# 1G_Eternet.net
KiCad netlist of a schematic drawn in Altium Designer
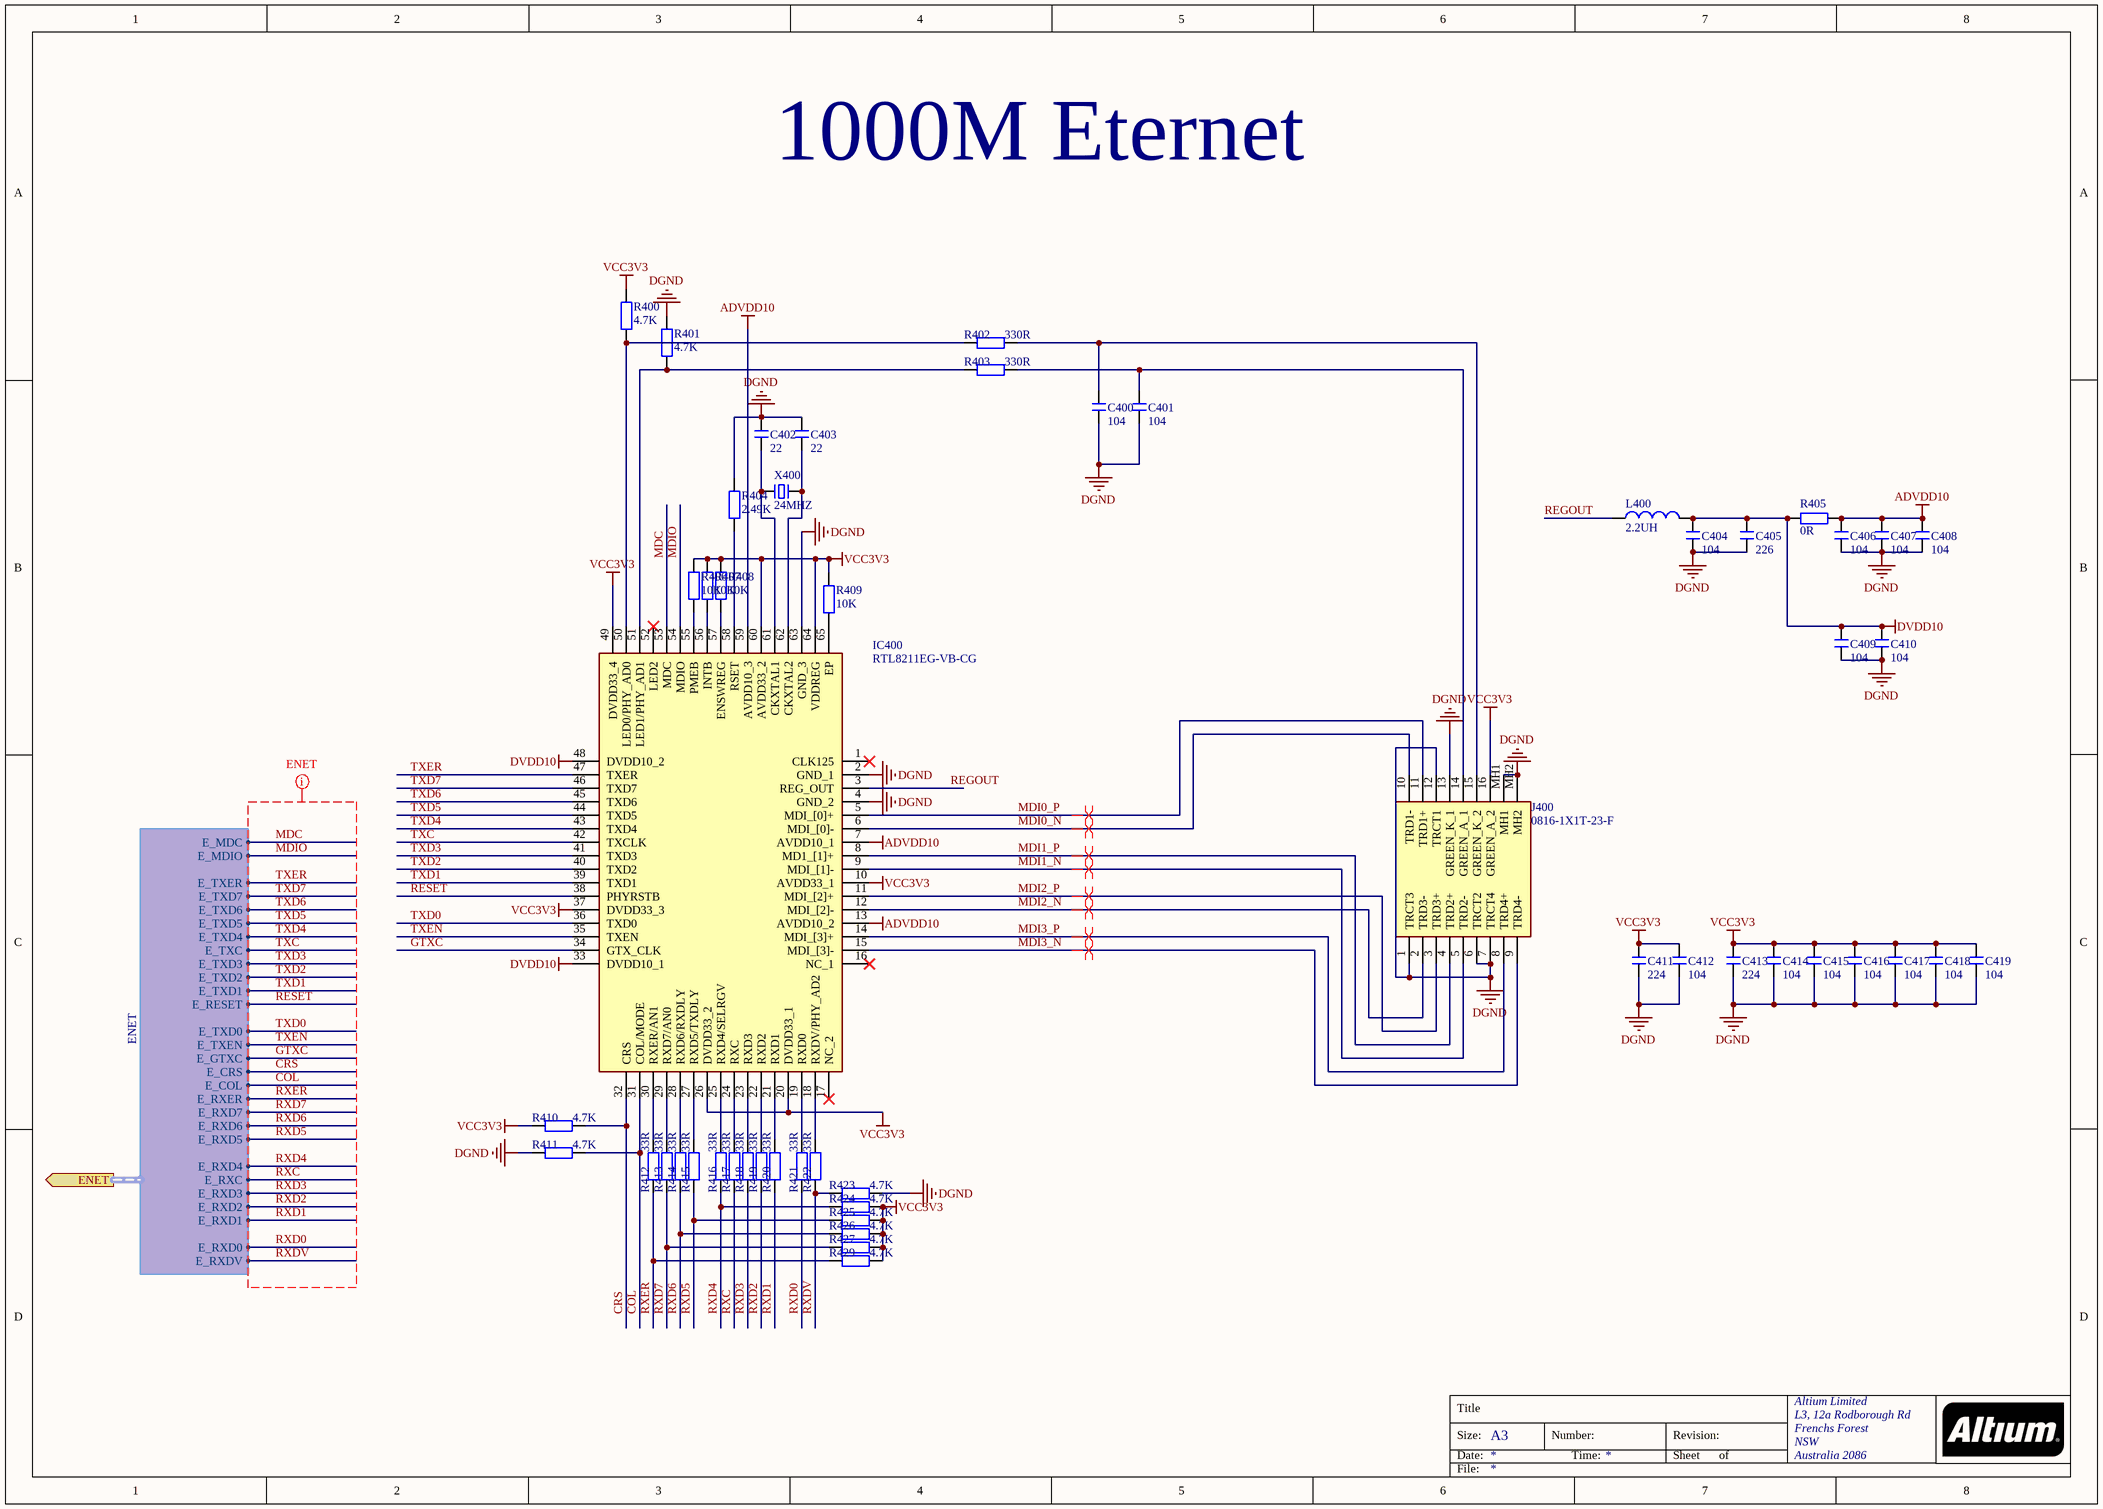
[diagram p0: 1G Eternet.SchDoc]

(export (version "E")
  (design (tool "Eeschema 10.0.6"))
  (components
    (comp (ref "C400")
      (value "104")
      (footprint "C 0402_M")
      (description "无极性贴片电容")
      (fields (field (name "版权归属") "源创客"))
      (libsource (lib "3.1   - 电阻-电容-电感") (part "C"))
    )
    (comp (ref "C401")
      (value "104")
      (footprint "C 0402_M")
      (description "无极性贴片电容")
      (fields (field (name "版权归属") "源创客"))
      (libsource (lib "3.1   - 电阻-电容-电感") (part "C"))
    )
    (comp (ref "C402")
      (value "22")
      (footprint "C 0402_M")
      (description "无极性贴片电容")
      (fields (field (name "版权归属") "源创客"))
      (libsource (lib "3.1   - 电阻-电容-电感") (part "C"))
    )
    (comp (ref "C403")
      (value "22")
      (footprint "C 0402_M")
      (description "无极性贴片电容")
      (fields (field (name "版权归属") "源创客"))
      (libsource (lib "3.1   - 电阻-电容-电感") (part "C"))
    )
    (comp (ref "C404")
      (value "104")
      (footprint "C 0402_M")
      (description "无极性贴片电容")
      (fields (field (name "版权归属") "源创客"))
      (libsource (lib "3.1   - 电阻-电容-电感") (part "C"))
    )
    (comp (ref "C405")
      (value "226")
      (footprint "C 0402_M")
      (description "无极性贴片电容")
      (fields (field (name "版权归属") "源创客"))
      (libsource (lib "3.1   - 电阻-电容-电感") (part "C"))
    )
    (comp (ref "C406")
      (value "104")
      (footprint "C 0402_M")
      (description "无极性贴片电容")
      (fields (field (name "版权归属") "源创客"))
      (libsource (lib "3.1   - 电阻-电容-电感") (part "C"))
    )
    (comp (ref "C407")
      (value "104")
      (footprint "C 0402_M")
      (description "无极性贴片电容")
      (fields (field (name "版权归属") "源创客"))
      (libsource (lib "3.1   - 电阻-电容-电感") (part "C"))
    )
    (comp (ref "C408")
      (value "104")
      (footprint "C 0402_M")
      (description "无极性贴片电容")
      (fields (field (name "版权归属") "源创客"))
      (libsource (lib "3.1   - 电阻-电容-电感") (part "C"))
    )
    (comp (ref "C409")
      (value "104")
      (footprint "C 0402_M")
      (description "无极性贴片电容")
      (fields (field (name "版权归属") "源创客"))
      (libsource (lib "3.1   - 电阻-电容-电感") (part "C"))
    )
    (comp (ref "C410")
      (value "104")
      (footprint "C 0402_M")
      (description "无极性贴片电容")
      (fields (field (name "版权归属") "源创客"))
      (libsource (lib "3.1   - 电阻-电容-电感") (part "C"))
    )
    (comp (ref "C411")
      (value "224")
      (footprint "C 0402_M")
      (description "无极性贴片电容")
      (fields (field (name "版权归属") "源创客"))
      (libsource (lib "3.1   - 电阻-电容-电感") (part "C"))
    )
    (comp (ref "C412")
      (value "104")
      (footprint "C 0402_M")
      (description "无极性贴片电容")
      (fields (field (name "版权归属") "源创客"))
      (libsource (lib "3.1   - 电阻-电容-电感") (part "C"))
    )
    (comp (ref "C413")
      (value "224")
      (footprint "C 0402_M")
      (description "无极性贴片电容")
      (fields (field (name "版权归属") "源创客"))
      (libsource (lib "3.1   - 电阻-电容-电感") (part "C"))
    )
    (comp (ref "C414")
      (value "104")
      (footprint "C 0402_M")
      (description "无极性贴片电容")
      (fields (field (name "版权归属") "源创客"))
      (libsource (lib "3.1   - 电阻-电容-电感") (part "C"))
    )
    (comp (ref "C415")
      (value "104")
      (footprint "C 0402_M")
      (description "无极性贴片电容")
      (fields (field (name "版权归属") "源创客"))
      (libsource (lib "3.1   - 电阻-电容-电感") (part "C"))
    )
    (comp (ref "C416")
      (value "104")
      (footprint "C 0402_M")
      (description "无极性贴片电容")
      (fields (field (name "版权归属") "源创客"))
      (libsource (lib "3.1   - 电阻-电容-电感") (part "C"))
    )
    (comp (ref "C417")
      (value "104")
      (footprint "C 0402_M")
      (description "无极性贴片电容")
      (fields (field (name "版权归属") "源创客"))
      (libsource (lib "3.1   - 电阻-电容-电感") (part "C"))
    )
    (comp (ref "C418")
      (value "104")
      (footprint "C 0402_M")
      (description "无极性贴片电容")
      (fields (field (name "版权归属") "源创客"))
      (libsource (lib "3.1   - 电阻-电容-电感") (part "C"))
    )
    (comp (ref "C419")
      (value "104")
      (footprint "C 0402_M")
      (description "无极性贴片电容")
      (fields (field (name "版权归属") "源创客"))
      (libsource (lib "3.1   - 电阻-电容-电感") (part "C"))
    )
    (comp (ref "IC400")
      (value "RTL8211EG-VB-CG")
      (footprint "PcbLib1:QFN50P900X900X100-65N-D")
      (description "Integrated Circuit")
      (libsource (lib "altium-import") (part "root_0_mirrored_RTL8211EG-VB-CG_"))
    )
    (comp (ref "J400")
      (value "0816-1X1T-23-F")
      (footprint "PcbLib1:08161X1T23F")
      (description "Connector")
      (fields (field (name "MOUSER PART NUMBER") "530-0816-1X1T-23-F"))
      (libsource (lib "altium-import") (part "root_1_0816-1X1T-23-F_"))
    )
    (comp (ref "L400")
      (value "2.2UH")
      (footprint "L 0805")
      (libsource (lib "altium-import") (part "root_1_INDUCTOR_"))
    )
    (comp (ref "R400")
      (value "4.7K")
      (footprint "R 0402_M")
      (description "贴片电阻")
      (fields (field (name "版权归属") "源创客"))
      (libsource (lib "3.1   - 电阻-电容-电感") (part "R"))
    )
    (comp (ref "R401")
      (value "4.7K")
      (footprint "R 0402_M")
      (description "贴片电阻")
      (fields (field (name "版权归属") "源创客"))
      (libsource (lib "3.1   - 电阻-电容-电感") (part "R"))
    )
    (comp (ref "R402")
      (value "330R")
      (footprint "R 0402_M")
      (description "贴片电阻")
      (fields (field (name "版权归属") "源创客"))
      (libsource (lib "3.1   - 电阻-电容-电感") (part "R"))
    )
    (comp (ref "R403")
      (value "330R")
      (footprint "R 0402_M")
      (description "贴片电阻")
      (fields (field (name "版权归属") "源创客"))
      (libsource (lib "3.1   - 电阻-电容-电感") (part "R"))
    )
    (comp (ref "R404")
      (value "2.49K")
      (footprint "R 0402_M")
      (description "贴片电阻")
      (fields (field (name "版权归属") "源创客"))
      (libsource (lib "3.1   - 电阻-电容-电感") (part "R"))
    )
    (comp (ref "R405")
      (value "0R")
      (footprint "R 0402_M")
      (description "贴片电阻")
      (fields (field (name "版权归属") "源创客"))
      (libsource (lib "3.1   - 电阻-电容-电感") (part "R"))
    )
    (comp (ref "R406")
      (value "10K")
      (footprint "R 0402_M")
      (description "贴片电阻")
      (fields (field (name "版权归属") "源创客"))
      (libsource (lib "3.1   - 电阻-电容-电感") (part "R"))
    )
    (comp (ref "R407")
      (value "10K")
      (footprint "R 0402_M")
      (description "贴片电阻")
      (fields (field (name "版权归属") "源创客"))
      (libsource (lib "3.1   - 电阻-电容-电感") (part "R"))
    )
    (comp (ref "R408")
      (value "10K")
      (footprint "R 0402_M")
      (description "贴片电阻")
      (fields (field (name "版权归属") "源创客"))
      (libsource (lib "3.1   - 电阻-电容-电感") (part "R"))
    )
    (comp (ref "R409")
      (value "10K")
      (footprint "R 0402_M")
      (description "贴片电阻")
      (fields (field (name "版权归属") "源创客"))
      (libsource (lib "3.1   - 电阻-电容-电感") (part "R"))
    )
    (comp (ref "R410")
      (value "4.7K")
      (footprint "R 0402_M")
      (description "贴片电阻")
      (fields (field (name "版权归属") "源创客"))
      (libsource (lib "3.1   - 电阻-电容-电感") (part "R"))
    )
    (comp (ref "R411")
      (value "4.7K")
      (footprint "R 0402_M")
      (description "贴片电阻")
      (fields (field (name "版权归属") "源创客"))
      (libsource (lib "3.1   - 电阻-电容-电感") (part "R"))
    )
    (comp (ref "R412")
      (value "33R")
      (footprint "R 0402_M")
      (description "贴片电阻")
      (fields (field (name "版权归属") "源创客"))
      (libsource (lib "3.1   - 电阻-电容-电感") (part "R"))
    )
    (comp (ref "R413")
      (value "33R")
      (footprint "R 0402_M")
      (description "贴片电阻")
      (fields (field (name "版权归属") "源创客"))
      (libsource (lib "3.1   - 电阻-电容-电感") (part "R"))
    )
    (comp (ref "R414")
      (value "33R")
      (footprint "R 0402_M")
      (description "贴片电阻")
      (fields (field (name "版权归属") "源创客"))
      (libsource (lib "3.1   - 电阻-电容-电感") (part "R"))
    )
    (comp (ref "R415")
      (value "33R")
      (footprint "R 0402_M")
      (description "贴片电阻")
      (fields (field (name "版权归属") "源创客"))
      (libsource (lib "3.1   - 电阻-电容-电感") (part "R"))
    )
    (comp (ref "R416")
      (value "33R")
      (footprint "R 0402_M")
      (description "贴片电阻")
      (fields (field (name "版权归属") "源创客"))
      (libsource (lib "3.1   - 电阻-电容-电感") (part "R"))
    )
    (comp (ref "R417")
      (value "33R")
      (footprint "R 0402_M")
      (description "贴片电阻")
      (fields (field (name "版权归属") "源创客"))
      (libsource (lib "3.1   - 电阻-电容-电感") (part "R"))
    )
    (comp (ref "R418")
      (value "33R")
      (footprint "R 0402_M")
      (description "贴片电阻")
      (fields (field (name "版权归属") "源创客"))
      (libsource (lib "3.1   - 电阻-电容-电感") (part "R"))
    )
    (comp (ref "R419")
      (value "33R")
      (footprint "R 0402_M")
      (description "贴片电阻")
      (fields (field (name "版权归属") "源创客"))
      (libsource (lib "3.1   - 电阻-电容-电感") (part "R"))
    )
    (comp (ref "R420")
      (value "33R")
      (footprint "R 0402_M")
      (description "贴片电阻")
      (fields (field (name "版权归属") "源创客"))
      (libsource (lib "3.1   - 电阻-电容-电感") (part "R"))
    )
    (comp (ref "R421")
      (value "33R")
      (footprint "R 0402_M")
      (description "贴片电阻")
      (fields (field (name "版权归属") "源创客"))
      (libsource (lib "3.1   - 电阻-电容-电感") (part "R"))
    )
    (comp (ref "R422")
      (value "33R")
      (footprint "R 0402_M")
      (description "贴片电阻")
      (fields (field (name "版权归属") "源创客"))
      (libsource (lib "3.1   - 电阻-电容-电感") (part "R"))
    )
    (comp (ref "R423")
      (value "4.7K")
      (footprint "R 0402_M")
      (description "贴片电阻")
      (fields (field (name "版权归属") "源创客"))
      (libsource (lib "3.1   - 电阻-电容-电感") (part "R"))
    )
    (comp (ref "R424")
      (value "4.7K")
      (footprint "R 0402_M")
      (description "贴片电阻")
      (fields (field (name "版权归属") "源创客"))
      (libsource (lib "3.1   - 电阻-电容-电感") (part "R"))
    )
    (comp (ref "R425")
      (value "4.7K")
      (footprint "R 0402_M")
      (description "贴片电阻")
      (fields (field (name "版权归属") "源创客"))
      (libsource (lib "3.1   - 电阻-电容-电感") (part "R"))
    )
    (comp (ref "R426")
      (value "4.7K")
      (footprint "R 0402_M")
      (description "贴片电阻")
      (fields (field (name "版权归属") "源创客"))
      (libsource (lib "3.1   - 电阻-电容-电感") (part "R"))
    )
    (comp (ref "R427")
      (value "4.7K")
      (footprint "R 0402_M")
      (description "贴片电阻")
      (fields (field (name "版权归属") "源创客"))
      (libsource (lib "3.1   - 电阻-电容-电感") (part "R"))
    )
    (comp (ref "R429")
      (value "4.7K")
      (footprint "R 0402_M")
      (description "贴片电阻")
      (fields (field (name "版权归属") "源创客"))
      (libsource (lib "3.1   - 电阻-电容-电感") (part "R"))
    )
    (comp (ref "X400")
      (value "24MHZ")
      (footprint "OSC 5032-2P")
      (description "2脚无源脚晶振")
      (fields (field (name "版权归属") "源创客"))
      (libsource (lib "10.1 - 保险丝-晶振") (part "XTAL-2P"))
    )
  )
  (nets
    (net (code "2") (name "/COL") (class "Default")
      (node (ref "IC400") (pin "31") (pinfunction "COL/MODE_31") (pintype "passive"))
      (node (ref "R411") (pin "1") (pinfunction "1_1") (pintype "passive"))
    )
    (net (code "3") (name "/CRS") (class "Default")
      (node (ref "IC400") (pin "32") (pinfunction "CRS_32") (pintype "passive"))
      (node (ref "R410") (pin "1") (pinfunction "1_1") (pintype "passive"))
    )
    (net (code "4") (name "/GTXC") (class "Default")
      (node (ref "IC400") (pin "34") (pinfunction "GTX_CLK_34") (pintype "passive"))
    )
    (net (code "5") (name "/MDC") (class "Default")
      (node (ref "IC400") (pin "53") (pinfunction "MDC_53") (pintype "passive"))
    )
    (net (code "6") (name "/MDI0_N") (class "Default")
      (node (ref "IC400") (pin "6") (pinfunction "MDI_[0]-_6") (pintype "passive"))
      (node (ref "J400") (pin "10") (pinfunction "TRD1-_10") (pintype "passive"))
    )
    (net (code "7") (name "/MDI0_P") (class "Default")
      (node (ref "IC400") (pin "5") (pinfunction "MDI_[0]+_5") (pintype "passive"))
      (node (ref "J400") (pin "11") (pinfunction "TRD1+_11") (pintype "passive"))
    )
    (net (code "8") (name "/MDI1_N") (class "Default")
      (node (ref "IC400") (pin "9") (pinfunction "MDI_[1]-_9") (pintype "passive"))
      (node (ref "J400") (pin "5") (pinfunction "TRD2-_5") (pintype "passive"))
    )
    (net (code "9") (name "/MDI1_P") (class "Default")
      (node (ref "IC400") (pin "8") (pinfunction "MD1_[1]+_8") (pintype "passive"))
      (node (ref "J400") (pin "4") (pinfunction "TRD2+_4") (pintype "passive"))
    )
    (net (code "10") (name "/MDI2_N") (class "Default")
      (node (ref "IC400") (pin "12") (pinfunction "MDI_[2]-_12") (pintype "passive"))
      (node (ref "J400") (pin "2") (pinfunction "TRD3-_2") (pintype "passive"))
    )
    (net (code "11") (name "/MDI2_P") (class "Default")
      (node (ref "IC400") (pin "11") (pinfunction "MDI_[2]+_11") (pintype "passive"))
      (node (ref "J400") (pin "3") (pinfunction "TRD3+_3") (pintype "passive"))
    )
    (net (code "12") (name "/MDI3_N") (class "Default")
      (node (ref "IC400") (pin "15") (pinfunction "MDI_[3]-_15") (pintype "passive"))
      (node (ref "J400") (pin "9") (pinfunction "TRD4-_9") (pintype "passive"))
    )
    (net (code "13") (name "/MDI3_P") (class "Default")
      (node (ref "IC400") (pin "14") (pinfunction "MDI_[3]+_14") (pintype "passive"))
      (node (ref "J400") (pin "8") (pinfunction "TRD4+_8") (pintype "passive"))
    )
    (net (code "14") (name "/MDIO") (class "Default")
      (node (ref "IC400") (pin "54") (pinfunction "MDIO_54") (pintype "passive"))
    )
    (net (code "15") (name "/REGOUT") (class "Default")
      (node (ref "IC400") (pin "3") (pinfunction "REG_OUT_3") (pintype "passive"))
      (node (ref "L400") (pin "1") (pinfunction "1_1") (pintype "passive"))
    )
    (net (code "16") (name "/RESET") (class "Default")
      (node (ref "IC400") (pin "38") (pinfunction "PHYRSTB_38") (pintype "passive"))
    )
    (net (code "17") (name "/RXC") (class "Default")
      (node (ref "R417") (pin "2") (pinfunction "2_2") (pintype "passive"))
    )
    (net (code "18") (name "/RXD0") (class "Default")
      (node (ref "R421") (pin "2") (pinfunction "2_2") (pintype "passive"))
    )
    (net (code "19") (name "/RXD1") (class "Default")
      (node (ref "R420") (pin "2") (pinfunction "2_2") (pintype "passive"))
    )
    (net (code "20") (name "/RXD2") (class "Default")
      (node (ref "R419") (pin "2") (pinfunction "2_2") (pintype "passive"))
    )
    (net (code "21") (name "/RXD3") (class "Default")
      (node (ref "R418") (pin "2") (pinfunction "2_2") (pintype "passive"))
    )
    (net (code "22") (name "/RXD4") (class "Default")
      (node (ref "R416") (pin "2") (pinfunction "2_2") (pintype "passive"))
      (node (ref "R424") (pin "1") (pinfunction "1_1") (pintype "passive"))
    )
    (net (code "23") (name "/RXD5") (class "Default")
      (node (ref "R415") (pin "2") (pinfunction "2_2") (pintype "passive"))
      (node (ref "R425") (pin "1") (pinfunction "1_1") (pintype "passive"))
    )
    (net (code "24") (name "/RXD6") (class "Default")
      (node (ref "R414") (pin "2") (pinfunction "2_2") (pintype "passive"))
      (node (ref "R426") (pin "1") (pinfunction "1_1") (pintype "passive"))
    )
    (net (code "25") (name "/RXD7") (class "Default")
      (node (ref "R413") (pin "2") (pinfunction "2_2") (pintype "passive"))
      (node (ref "R427") (pin "1") (pinfunction "1_1") (pintype "passive"))
    )
    (net (code "26") (name "/RXDV") (class "Default")
      (node (ref "R422") (pin "2") (pinfunction "2_2") (pintype "passive"))
      (node (ref "R423") (pin "1") (pinfunction "1_1") (pintype "passive"))
    )
    (net (code "27") (name "/RXER") (class "Default")
      (node (ref "R412") (pin "2") (pinfunction "2_2") (pintype "passive"))
      (node (ref "R429") (pin "1") (pinfunction "1_1") (pintype "passive"))
    )
    (net (code "28") (name "/TXC") (class "Default")
      (node (ref "IC400") (pin "42") (pinfunction "TXCLK_42") (pintype "passive"))
    )
    (net (code "29") (name "/TXD0") (class "Default")
      (node (ref "IC400") (pin "36") (pinfunction "TXD0_36") (pintype "passive"))
    )
    (net (code "30") (name "/TXD1") (class "Default")
      (node (ref "IC400") (pin "39") (pinfunction "TXD1_39") (pintype "passive"))
    )
    (net (code "31") (name "/TXD2") (class "Default")
      (node (ref "IC400") (pin "40") (pinfunction "TXD2_40") (pintype "passive"))
    )
    (net (code "32") (name "/TXD3") (class "Default")
      (node (ref "IC400") (pin "41") (pinfunction "TXD3_41") (pintype "passive"))
    )
    (net (code "33") (name "/TXD4") (class "Default")
      (node (ref "IC400") (pin "43") (pinfunction "TXD4_43") (pintype "passive"))
    )
    (net (code "34") (name "/TXD5") (class "Default")
      (node (ref "IC400") (pin "44") (pinfunction "TXD5_44") (pintype "passive"))
    )
    (net (code "35") (name "/TXD6") (class "Default")
      (node (ref "IC400") (pin "45") (pinfunction "TXD6_45") (pintype "passive"))
    )
    (net (code "36") (name "/TXD7") (class "Default")
      (node (ref "IC400") (pin "46") (pinfunction "TXD7_46") (pintype "passive"))
    )
    (net (code "37") (name "/TXEN") (class "Default")
      (node (ref "IC400") (pin "35") (pinfunction "TXEN_35") (pintype "passive"))
    )
    (net (code "38") (name "/TXER") (class "Default")
      (node (ref "IC400") (pin "47") (pinfunction "TXER_47") (pintype "passive"))
    )
    (net (code "40") (name "ADVDD10") (class "Default")
      (node (ref "C406") (pin "2") (pinfunction "2_2") (pintype "passive"))
      (node (ref "C407") (pin "2") (pinfunction "2_2") (pintype "passive"))
      (node (ref "C408") (pin "2") (pinfunction "2_2") (pintype "passive"))
      (node (ref "IC400") (pin "13") (pinfunction "AVDD10_2_13") (pintype "passive"))
      (node (ref "IC400") (pin "59") (pinfunction "AVDD10_3_59") (pintype "passive"))
      (node (ref "IC400") (pin "7") (pinfunction "AVDD10_1_7") (pintype "passive"))
      (node (ref "R405") (pin "2") (pinfunction "2_2") (pintype "passive"))
    )
    (net (code "41") (name "DGND") (class "Default")
      (node (ref "C400") (pin "1") (pinfunction "1_1") (pintype "passive"))
      (node (ref "C401") (pin "1") (pinfunction "1_1") (pintype "passive"))
      (node (ref "C402") (pin "2") (pinfunction "2_2") (pintype "passive"))
      (node (ref "C403") (pin "2") (pinfunction "2_2") (pintype "passive"))
      (node (ref "C404") (pin "1") (pinfunction "1_1") (pintype "passive"))
      (node (ref "C405") (pin "1") (pinfunction "1_1") (pintype "passive"))
      (node (ref "C406") (pin "1") (pinfunction "1_1") (pintype "passive"))
      (node (ref "C407") (pin "1") (pinfunction "1_1") (pintype "passive"))
      (node (ref "C408") (pin "1") (pinfunction "1_1") (pintype "passive"))
      (node (ref "C409") (pin "1") (pinfunction "1_1") (pintype "passive"))
      (node (ref "C410") (pin "1") (pinfunction "1_1") (pintype "passive"))
      (node (ref "C411") (pin "1") (pinfunction "1_1") (pintype "passive"))
      (node (ref "C412") (pin "1") (pinfunction "1_1") (pintype "passive"))
      (node (ref "C413") (pin "1") (pinfunction "1_1") (pintype "passive"))
      (node (ref "C414") (pin "1") (pinfunction "1_1") (pintype "passive"))
      (node (ref "C415") (pin "1") (pinfunction "1_1") (pintype "passive"))
      (node (ref "C416") (pin "1") (pinfunction "1_1") (pintype "passive"))
      (node (ref "C417") (pin "1") (pinfunction "1_1") (pintype "passive"))
      (node (ref "C418") (pin "1") (pinfunction "1_1") (pintype "passive"))
      (node (ref "C419") (pin "1") (pinfunction "1_1") (pintype "passive"))
      (node (ref "IC400") (pin "2") (pinfunction "GND_1_2") (pintype "passive"))
      (node (ref "IC400") (pin "4") (pinfunction "GND_2_4") (pintype "passive"))
      (node (ref "IC400") (pin "63") (pinfunction "GND_3_63") (pintype "passive"))
      (node (ref "J400") (pin "1") (pinfunction "TRCT3_1") (pintype "passive"))
      (node (ref "J400") (pin "12") (pinfunction "TRCT1_12") (pintype "passive"))
      (node (ref "J400") (pin "13") (pinfunction "GREEN_K_1_13") (pintype "passive"))
      (node (ref "J400") (pin "6") (pinfunction "TRCT2_6") (pintype "passive"))
      (node (ref "J400") (pin "7") (pinfunction "TRCT4_7") (pintype "passive"))
      (node (ref "J400") (pin "MH1") (pinfunction "MH1_MH1") (pintype "passive"))
      (node (ref "J400") (pin "MH2") (pinfunction "MH2_MH2") (pintype "passive"))
      (node (ref "R401") (pin "1") (pinfunction "1_1") (pintype "passive"))
      (node (ref "R404") (pin "1") (pinfunction "1_1") (pintype "passive"))
      (node (ref "R411") (pin "2") (pinfunction "2_2") (pintype "passive"))
      (node (ref "R423") (pin "2") (pinfunction "2_2") (pintype "passive"))
    )
    (net (code "42") (name "DVDD10") (class "Default")
      (node (ref "C404") (pin "2") (pinfunction "2_2") (pintype "passive"))
      (node (ref "C405") (pin "2") (pinfunction "2_2") (pintype "passive"))
      (node (ref "C409") (pin "2") (pinfunction "2_2") (pintype "passive"))
      (node (ref "C410") (pin "2") (pinfunction "2_2") (pintype "passive"))
      (node (ref "IC400") (pin "33") (pinfunction "DVDD10_1_33") (pintype "passive"))
      (node (ref "IC400") (pin "48") (pinfunction "DVDD10_2_48") (pintype "passive"))
      (node (ref "L400") (pin "2") (pinfunction "2_2") (pintype "passive"))
      (node (ref "R405") (pin "1") (pinfunction "1_1") (pintype "passive"))
    )
    (net (code "43") (name "Net-(IC400-CKXTAL1)") (class "Default")
      (node (ref "C402") (pin "1") (pinfunction "1_1") (pintype "passive"))
      (node (ref "IC400") (pin "61") (pinfunction "CKXTAL1_61") (pintype "passive"))
      (node (ref "X400") (pin "2") (pinfunction "2_2") (pintype "passive"))
    )
    (net (code "44") (name "Net-(IC400-CKXTAL2)") (class "Default")
      (node (ref "C403") (pin "1") (pinfunction "1_1") (pintype "passive"))
      (node (ref "IC400") (pin "62") (pinfunction "CKXTAL2_62") (pintype "passive"))
      (node (ref "X400") (pin "1") (pinfunction "1_1") (pintype "passive"))
    )
    (net (code "45") (name "Net-(IC400-ENSWREG)") (class "Default")
      (node (ref "IC400") (pin "57") (pinfunction "ENSWREG_57") (pintype "passive"))
      (node (ref "R408") (pin "2") (pinfunction "2_2") (pintype "passive"))
    )
    (net (code "46") (name "Net-(IC400-EP)") (class "Default")
      (node (ref "IC400") (pin "65") (pinfunction "EP_65") (pintype "passive"))
      (node (ref "R409") (pin "2") (pinfunction "2_2") (pintype "passive"))
    )
    (net (code "47") (name "Net-(IC400-INTB)") (class "Default")
      (node (ref "IC400") (pin "56") (pinfunction "INTB_56") (pintype "passive"))
      (node (ref "R407") (pin "2") (pinfunction "2_2") (pintype "passive"))
    )
    (net (code "48") (name "Net-(IC400-LED0{slash}PHY_AD0)") (class "Default")
      (node (ref "IC400") (pin "50") (pinfunction "LED0/PHY_AD0_50") (pintype "passive"))
      (node (ref "R400") (pin "2") (pinfunction "2_2") (pintype "passive"))
      (node (ref "R402") (pin "2") (pinfunction "2_2") (pintype "passive"))
    )
    (net (code "49") (name "Net-(IC400-LED1{slash}PHY_AD1)") (class "Default")
      (node (ref "IC400") (pin "51") (pinfunction "LED1/PHY_AD1_51") (pintype "passive"))
      (node (ref "R401") (pin "2") (pinfunction "2_2") (pintype "passive"))
      (node (ref "R403") (pin "2") (pinfunction "2_2") (pintype "passive"))
    )
    (net (code "50") (name "Net-(IC400-PMEB)") (class "Default")
      (node (ref "IC400") (pin "55") (pinfunction "PMEB_55") (pintype "passive"))
      (node (ref "R406") (pin "2") (pinfunction "2_2") (pintype "passive"))
    )
    (net (code "51") (name "Net-(IC400-RSET)") (class "Default")
      (node (ref "IC400") (pin "58") (pinfunction "RSET_58") (pintype "passive"))
      (node (ref "R404") (pin "2") (pinfunction "2_2") (pintype "passive"))
    )
    (net (code "52") (name "Net-(IC400-RXC)") (class "Default")
      (node (ref "IC400") (pin "24") (pinfunction "RXC_24") (pintype "passive"))
      (node (ref "R417") (pin "1") (pinfunction "1_1") (pintype "passive"))
    )
    (net (code "53") (name "Net-(IC400-RXD0)") (class "Default")
      (node (ref "IC400") (pin "19") (pinfunction "RXD0_19") (pintype "passive"))
      (node (ref "R421") (pin "1") (pinfunction "1_1") (pintype "passive"))
    )
    (net (code "54") (name "Net-(IC400-RXD1)") (class "Default")
      (node (ref "IC400") (pin "21") (pinfunction "RXD1_21") (pintype "passive"))
      (node (ref "R420") (pin "1") (pinfunction "1_1") (pintype "passive"))
    )
    (net (code "55") (name "Net-(IC400-RXD2)") (class "Default")
      (node (ref "IC400") (pin "22") (pinfunction "RXD2_22") (pintype "passive"))
      (node (ref "R419") (pin "1") (pinfunction "1_1") (pintype "passive"))
    )
    (net (code "56") (name "Net-(IC400-RXD3)") (class "Default")
      (node (ref "IC400") (pin "23") (pinfunction "RXD3_23") (pintype "passive"))
      (node (ref "R418") (pin "1") (pinfunction "1_1") (pintype "passive"))
    )
    (net (code "57") (name "Net-(IC400-RXD4{slash}SELRGV)") (class "Default")
      (node (ref "IC400") (pin "25") (pinfunction "RXD4/SELRGV_25") (pintype "passive"))
      (node (ref "R416") (pin "1") (pinfunction "1_1") (pintype "passive"))
    )
    (net (code "58") (name "Net-(IC400-RXD5{slash}TXDLY)") (class "Default")
      (node (ref "IC400") (pin "27") (pinfunction "RXD5/TXDLY_27") (pintype "passive"))
      (node (ref "R415") (pin "1") (pinfunction "1_1") (pintype "passive"))
    )
    (net (code "59") (name "Net-(IC400-RXD6{slash}RXDLY)") (class "Default")
      (node (ref "IC400") (pin "28") (pinfunction "RXD6/RXDLY_28") (pintype "passive"))
      (node (ref "R414") (pin "1") (pinfunction "1_1") (pintype "passive"))
    )
    (net (code "60") (name "Net-(IC400-RXD7{slash}AN0)") (class "Default")
      (node (ref "IC400") (pin "29") (pinfunction "RXD7/AN0_29") (pintype "passive"))
      (node (ref "R413") (pin "1") (pinfunction "1_1") (pintype "passive"))
    )
    (net (code "61") (name "Net-(IC400-RXDV{slash}PHY_AD2)") (class "Default")
      (node (ref "IC400") (pin "18") (pinfunction "RXDV/PHY_AD2_18") (pintype "passive"))
      (node (ref "R422") (pin "1") (pinfunction "1_1") (pintype "passive"))
    )
    (net (code "62") (name "Net-(IC400-RXER{slash}AN1)") (class "Default")
      (node (ref "IC400") (pin "30") (pinfunction "RXER/AN1_30") (pintype "passive"))
      (node (ref "R412") (pin "1") (pinfunction "1_1") (pintype "passive"))
    )
    (net (code "63") (name "Net-(J400-GREEN_A_1)") (class "Default")
      (node (ref "C401") (pin "2") (pinfunction "2_2") (pintype "passive"))
      (node (ref "J400") (pin "14") (pinfunction "GREEN_A_1_14") (pintype "passive"))
      (node (ref "R403") (pin "1") (pinfunction "1_1") (pintype "passive"))
    )
    (net (code "64") (name "Net-(J400-GREEN_K_2)") (class "Default")
      (node (ref "C400") (pin "2") (pinfunction "2_2") (pintype "passive"))
      (node (ref "J400") (pin "15") (pinfunction "GREEN_K_2_15") (pintype "passive"))
      (node (ref "R402") (pin "1") (pinfunction "1_1") (pintype "passive"))
    )
    (net (code "65") (name "VCC3V3") (class "Default")
      (node (ref "C411") (pin "2") (pinfunction "2_2") (pintype "passive"))
      (node (ref "C412") (pin "2") (pinfunction "2_2") (pintype "passive"))
      (node (ref "C413") (pin "2") (pinfunction "2_2") (pintype "passive"))
      (node (ref "C414") (pin "2") (pinfunction "2_2") (pintype "passive"))
      (node (ref "C415") (pin "2") (pinfunction "2_2") (pintype "passive"))
      (node (ref "C416") (pin "2") (pinfunction "2_2") (pintype "passive"))
      (node (ref "C417") (pin "2") (pinfunction "2_2") (pintype "passive"))
      (node (ref "C418") (pin "2") (pinfunction "2_2") (pintype "passive"))
      (node (ref "C419") (pin "2") (pinfunction "2_2") (pintype "passive"))
      (node (ref "IC400") (pin "10") (pinfunction "AVDD33_1_10") (pintype "passive"))
      (node (ref "IC400") (pin "20") (pinfunction "DVDD33_1_20") (pintype "passive"))
      (node (ref "IC400") (pin "26") (pinfunction "DVDD33_2_26") (pintype "passive"))
      (node (ref "IC400") (pin "37") (pinfunction "DVDD33_3_37") (pintype "passive"))
      (node (ref "IC400") (pin "49") (pinfunction "DVDD33_4_49") (pintype "passive"))
      (node (ref "IC400") (pin "60") (pinfunction "AVDD33_2_60") (pintype "passive"))
      (node (ref "IC400") (pin "64") (pinfunction "VDDREG_64") (pintype "passive"))
      (node (ref "J400") (pin "16") (pinfunction "GREEN_A_2_16") (pintype "passive"))
      (node (ref "R400") (pin "1") (pinfunction "1_1") (pintype "passive"))
      (node (ref "R406") (pin "1") (pinfunction "1_1") (pintype "passive"))
      (node (ref "R407") (pin "1") (pinfunction "1_1") (pintype "passive"))
      (node (ref "R408") (pin "1") (pinfunction "1_1") (pintype "passive"))
      (node (ref "R409") (pin "1") (pinfunction "1_1") (pintype "passive"))
      (node (ref "R410") (pin "2") (pinfunction "2_2") (pintype "passive"))
      (node (ref "R424") (pin "2") (pinfunction "2_2") (pintype "passive"))
      (node (ref "R425") (pin "2") (pinfunction "2_2") (pintype "passive"))
      (node (ref "R426") (pin "2") (pinfunction "2_2") (pintype "passive"))
      (node (ref "R427") (pin "2") (pinfunction "2_2") (pintype "passive"))
      (node (ref "R429") (pin "2") (pinfunction "2_2") (pintype "passive"))
    )
    (net (code "66") (name "unconnected-(IC400-CLK125-Pad1)") (class "Default")
      (node (ref "IC400") (pin "1") (pinfunction "CLK125_1") (pintype "passive+no_connect"))
    )
    (net (code "67") (name "unconnected-(IC400-LED2-Pad52)") (class "Default")
      (node (ref "IC400") (pin "52") (pinfunction "LED2_52") (pintype "passive+no_connect"))
    )
    (net (code "68") (name "unconnected-(IC400-NC_1-Pad16)") (class "Default")
      (node (ref "IC400") (pin "16") (pinfunction "NC_1_16") (pintype "passive+no_connect"))
    )
    (net (code "69") (name "unconnected-(IC400-NC_2-Pad17)") (class "Default")
      (node (ref "IC400") (pin "17") (pinfunction "NC_2_17") (pintype "passive+no_connect"))
    )
  )
)
